# Sheet1.net
KiCad netlist of a schematic drawn in Altium Designer
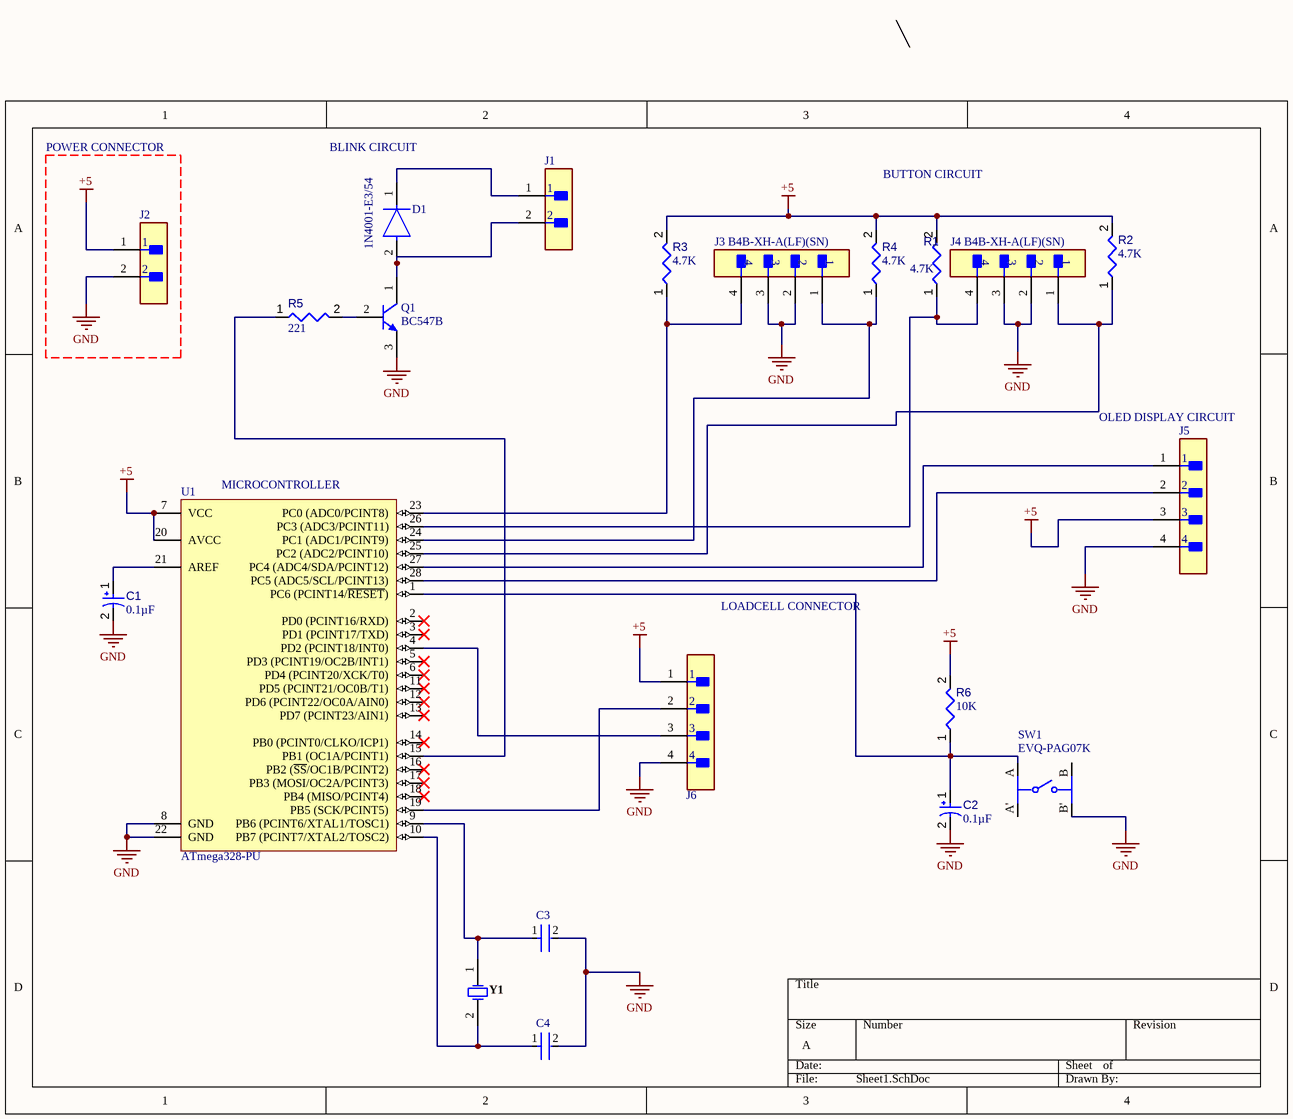
[diagram p0: Sheet1.SchDoc]

(export (version "E")
  (design (tool "Eeschema 10.0.6"))
  (components
    (comp (ref "C1")
      (value "0.1µF")
      (footprint "CAPPR55-200-1100X500X1200")
      (description "Aluminum Electrolytic Capacitor, 1 uF, +/- 20%, 50 V, -55 to 105 degC, 2-Pin THD, RoHS, Bulk")
      (fields (field (name "TOLERANCE") "20%") (field (name "MANUFACTURER") "Panasonic"))
      (libsource (lib "University of Moratuwa") (part "CAP-P-2"))
    )
    (comp (ref "C2")
      (value "0.1µF")
      (footprint "CAPPR55-200-1100X500X1200")
      (description "Aluminum Electrolytic Capacitor, 1 uF, +/- 20%, 50 V, -55 to 105 degC, 2-Pin THD, RoHS, Bulk")
      (fields (field (name "TOLERANCE") "20%") (field (name "MANUFACTURER") "Panasonic"))
      (libsource (lib "University of Moratuwa") (part "CAP-P-2"))
    )
    (comp (ref "C3")
      (value "RCE5C1H220J0M1H03A")
      (footprint "FP-RCE0K1-MFG")
      (description "Cap Ceramic 22pF 50V C0G ±5% Radial 5mm +125°C Automotive Bulk")
      (fields (field (name "TOLERANCE") "5%"))
      (libsource (lib "Altium Content Vault") (part "b4654b650e69147ec39a6b967a45e02"))
    )
    (comp (ref "C4")
      (value "RCE5C1H220J0M1H03A")
      (footprint "FP-RCE0K1-MFG")
      (description "Cap Ceramic 22pF 50V C0G ±5% Radial 5mm +125°C Automotive Bulk")
      (fields (field (name "TOLERANCE") "5%"))
      (libsource (lib "Altium Content Vault") (part "b4654b650e69147ec39a6b967a45e02"))
    )
    (comp (ref "D1")
      (value "1N4001-E3/54")
      (footprint "FP-1N4001-E3-54-MFG")
      (description "DIODE GEN PURP 50V 1A DO204AL")
      (fields (field (name "VOLTAGE") "50V"))
      (libsource (lib "Altium Content Vault") (part "d7152d700b627762746794eb795d46e"))
    )
    (comp (ref "J1")
      (value "~")
      (footprint "FP-B2B-XH-A_LF_SN-MFG")
      (description "CONN HEADER VERT 2POS 2.5MM")
      (libsource (lib "Altium Content Vault") (part "3bc925449376181038e59eaffc5286c"))
    )
    (comp (ref "J2")
      (value "~")
      (footprint "FP-B2B-XH-A_LF_SN-MFG")
      (description "CONN HEADER VERT 2POS 2.5MM")
      (libsource (lib "Altium Content Vault") (part "3bc925449376181038e59eaffc5286c"))
    )
    (comp (ref "J3")
      (value "B4B-XH-A(LF)(SN)")
      (footprint "FP-B4B-XH-A_LF_SN-MFG")
      (description "CONN HEADER VERT 4POS 2.5MM")
      (libsource (lib "Altium Content Vault") (part "299a8cea1bdcbc3624fe62c390fa72c"))
    )
    (comp (ref "J4")
      (value "B4B-XH-A(LF)(SN)")
      (footprint "FP-B4B-XH-A_LF_SN-MFG")
      (description "CONN HEADER VERT 4POS 2.5MM")
      (libsource (lib "Altium Content Vault") (part "299a8cea1bdcbc3624fe62c390fa72c"))
    )
    (comp (ref "J5")
      (value "B4B-XH-A(LF)(SN)")
      (footprint "FP-B4B-XH-A_LF_SN-MFG")
      (description "CONN HEADER VERT 4POS 2.5MM")
      (libsource (lib "Altium Content Vault") (part "299a8cea1bdcbc3624fe62c390fa72c"))
    )
    (comp (ref "J6")
      (value "B4B-XH-A(LF)(SN)")
      (footprint "FP-B4B-XH-A_LF_SN-MFG")
      (description "CONN HEADER VERT 4POS 2.5MM")
      (libsource (lib "Altium Content Vault") (part "299a8cea1bdcbc3624fe62c390fa72c"))
    )
    (comp (ref "Q1")
      (value "BC547B")
      (footprint "ONSC-TO-92-3-29-11")
      (description "Amplifier Transistor, NPN Silicon, 3-Pin TO-92, Bulk Box")
      (fields (field (name "MANUFACTURER") "On Semiconductor"))
      (libsource (lib "Altium Content Vault") (part "ONSC-NPN-C1B2E3-3"))
    )
    (comp (ref "R1")
      (value "4.7K")
      (footprint "RESA60-630X240")
      (description "Axial Resistor, 22.1 Ohm, +/- 1%, 250 mW, -55 to 155 degC, 2-Pin THD, RoHS, Bulk")
      (fields (field (name "POWER") "250mW") (field (name "MANUFACTURER") "Yageo"))
      (libsource (lib "University of Moratuwa") (part "RES-2"))
    )
    (comp (ref "R2")
      (value "4.7K")
      (footprint "RESA60-630X240")
      (description "Axial Resistor, 22.1 Ohm, +/- 1%, 250 mW, -55 to 155 degC, 2-Pin THD, RoHS, Bulk")
      (fields (field (name "POWER") "250mW") (field (name "MANUFACTURER") "Yageo"))
      (libsource (lib "University of Moratuwa") (part "RES-2"))
    )
    (comp (ref "R3")
      (value "4.7K")
      (footprint "RESA60-630X240")
      (description "Axial Resistor, 22.1 Ohm, +/- 1%, 250 mW, -55 to 155 degC, 2-Pin THD, RoHS, Bulk")
      (fields (field (name "POWER") "250mW") (field (name "MANUFACTURER") "Yageo"))
      (libsource (lib "University of Moratuwa") (part "RES-2"))
    )
    (comp (ref "R4")
      (value "4.7K")
      (footprint "RESA60-630X240")
      (description "Axial Resistor, 22.1 Ohm, +/- 1%, 250 mW, -55 to 155 degC, 2-Pin THD, RoHS, Bulk")
      (fields (field (name "POWER") "250mW") (field (name "MANUFACTURER") "Yageo"))
      (libsource (lib "University of Moratuwa") (part "RES-2"))
    )
    (comp (ref "R5")
      (value "221")
      (footprint "RESA60-630X240")
      (description "Axial Resistor, 221 Ohm, +/- 1%, 250 mW, -55 to 155 degC, 2-Pin THD, RoHS, Bulk")
      (fields (field (name "POWER") "250mW") (field (name "TOLERANCE") "1%"))
      (libsource (lib "University of Moratuwa") (part "RES-2"))
    )
    (comp (ref "R6")
      (value "10K")
      (footprint "RESA60-630X240")
      (description "Axial Resistor, 22.1 Ohm, +/- 1%, 250 mW, -55 to 155 degC, 2-Pin THD, RoHS, Bulk")
      (fields (field (name "POWER") "250mW") (field (name "MANUFACTURER") "Yageo"))
      (libsource (lib "University of Moratuwa") (part "RES-2"))
    )
    (comp (ref "SW1")
      (value "EVQ-PAG07K")
      (footprint "FP-EVQ-PAG07K-MFG")
      (description "SWITCH TACTILE SPST-NO 0.02A 15V")
      (libsource (lib "Altium Content Vault") (part "75038bc65b1af1a6bd057da08483287"))
    )
    (comp (ref "U1")
      (value "ATmega328-PU")
      (footprint "28P3")
      (libsource (lib "Altium Content Vault") (part "MC-8B-ATM48-IL28"))
    )
    (comp (ref "Y1")
      (value "HC-49US 16.000MHZ")
      (footprint "JPY-HC-49US")
      (description "Crystal, 16 MHz, +/- 30 ppm, 18 pF, -20 to 70 degC, 2-Pin THD")
      (fields (field (name "MANUFACTURER") "Jing peng yuan"))
      (libsource (lib "University of Moratuwa") (part "XTAL-1-2-2"))
    )
  )
  (nets
    (net (code "1") (name "+5") (class "Default")
      (node (ref "J2") (pin "1") (pinfunction "1_1") (pintype "passive"))
      (node (ref "J5") (pin "3") (pinfunction "3_3") (pintype "passive"))
      (node (ref "J6") (pin "1") (pinfunction "1_1") (pintype "passive"))
      (node (ref "R1") (pin "2") (pinfunction "2_2") (pintype "passive"))
      (node (ref "R2") (pin "2") (pinfunction "2_2") (pintype "passive"))
      (node (ref "R3") (pin "2") (pinfunction "2_2") (pintype "passive"))
      (node (ref "R4") (pin "2") (pinfunction "2_2") (pintype "passive"))
      (node (ref "R6") (pin "2") (pinfunction "2_2") (pintype "passive"))
      (node (ref "U1") (pin "20") (pinfunction "AVCC_20") (pintype "power_in"))
      (node (ref "U1") (pin "7") (pinfunction "VCC_7") (pintype "power_in"))
    )
    (net (code "2") (name "GND") (class "Default")
      (node (ref "C1") (pin "2") (pinfunction "2_2") (pintype "passive"))
      (node (ref "C2") (pin "2") (pinfunction "2_2") (pintype "passive"))
      (node (ref "C3") (pin "2") (pinfunction "2_2") (pintype "passive"))
      (node (ref "C4") (pin "2") (pinfunction "2_2") (pintype "passive"))
      (node (ref "J2") (pin "2") (pinfunction "2_2") (pintype "passive"))
      (node (ref "J3") (pin "2") (pinfunction "2_2") (pintype "passive"))
      (node (ref "J3") (pin "3") (pinfunction "3_3") (pintype "passive"))
      (node (ref "J4") (pin "2") (pinfunction "2_2") (pintype "passive"))
      (node (ref "J4") (pin "3") (pinfunction "3_3") (pintype "passive"))
      (node (ref "J5") (pin "4") (pinfunction "4_4") (pintype "passive"))
      (node (ref "J6") (pin "4") (pinfunction "4_4") (pintype "passive"))
      (node (ref "Q1") (pin "3") (pinfunction "E_3") (pintype "passive"))
      (node (ref "SW1") (pin "B'") (pinfunction "B'_B'") (pintype "passive"))
      (node (ref "U1") (pin "22") (pinfunction "GND_22") (pintype "power_in"))
      (node (ref "U1") (pin "8") (pinfunction "GND_8") (pintype "power_in"))
    )
    (net (code "3") (name "Net-(D1-A)") (class "Default")
      (node (ref "D1") (pin "2") (pinfunction "A_2") (pintype "passive"))
      (node (ref "J1") (pin "2") (pinfunction "2_2") (pintype "passive"))
      (node (ref "Q1") (pin "1") (pinfunction "C_1") (pintype "passive"))
    )
    (net (code "4") (name "Net-(D1-C)") (class "Default")
      (node (ref "D1") (pin "1") (pinfunction "C_1") (pintype "passive"))
      (node (ref "J1") (pin "1") (pinfunction "1_1") (pintype "passive"))
    )
    (net (code "5") (name "Net-(Q1-B)") (class "Default")
      (node (ref "Q1") (pin "2") (pinfunction "B_2") (pintype "passive"))
      (node (ref "R5") (pin "2") (pinfunction "2_2") (pintype "passive"))
    )
    (net (code "6") (name "Net-(U1-AREF)") (class "Default")
      (node (ref "C1") (pin "1") (pinfunction "1_1") (pintype "passive"))
      (node (ref "U1") (pin "21") (pinfunction "AREF_21") (pintype "power_in"))
    )
    (net (code "7") (name "Net-(U1-PB1_(OC1A{slash}PCINT1))") (class "Default")
      (node (ref "R5") (pin "1") (pinfunction "1_1") (pintype "passive"))
      (node (ref "U1") (pin "15") (pinfunction "PB1_(OC1A/PCINT1)_15") (pintype "bidirectional"))
    )
    (net (code "8") (name "Net-(U1-PB5_(SCK{slash}PCINT5))") (class "Default")
      (node (ref "J6") (pin "2") (pinfunction "2_2") (pintype "passive"))
      (node (ref "U1") (pin "19") (pinfunction "PB5_(SCK/PCINT5)_19") (pintype "bidirectional"))
    )
    (net (code "9") (name "Net-(U1-PB6_(PCINT6{slash}XTAL1{slash}TOSC1))") (class "Default")
      (node (ref "C3") (pin "1") (pinfunction "1_1") (pintype "passive"))
      (node (ref "U1") (pin "9") (pinfunction "PB6_(PCINT6/XTAL1/TOSC1)_9") (pintype "bidirectional"))
      (node (ref "Y1") (pin "1") (pinfunction "1_1") (pintype "passive"))
    )
    (net (code "10") (name "Net-(U1-PB7_(PCINT7{slash}XTAL2{slash}TOSC2))") (class "Default")
      (node (ref "C4") (pin "1") (pinfunction "1_1") (pintype "passive"))
      (node (ref "U1") (pin "10") (pinfunction "PB7_(PCINT7/XTAL2/TOSC2)_10") (pintype "bidirectional"))
      (node (ref "Y1") (pin "2") (pinfunction "2_2") (pintype "passive"))
    )
    (net (code "11") (name "Net-(U1-PC0_(ADC0{slash}PCINT8))") (class "Default")
      (node (ref "J3") (pin "4") (pinfunction "4_4") (pintype "passive"))
      (node (ref "R3") (pin "1") (pinfunction "1_1") (pintype "passive"))
      (node (ref "U1") (pin "23") (pinfunction "PC0_(ADC0/PCINT8)_23") (pintype "bidirectional"))
    )
    (net (code "12") (name "Net-(U1-PC1_(ADC1{slash}PCINT9))") (class "Default")
      (node (ref "J3") (pin "1") (pinfunction "1_1") (pintype "passive"))
      (node (ref "R4") (pin "1") (pinfunction "1_1") (pintype "passive"))
      (node (ref "U1") (pin "24") (pinfunction "PC1_(ADC1/PCINT9)_24") (pintype "bidirectional"))
    )
    (net (code "13") (name "Net-(U1-PC2_(ADC2{slash}PCINT10))") (class "Default")
      (node (ref "J4") (pin "1") (pinfunction "1_1") (pintype "passive"))
      (node (ref "R2") (pin "1") (pinfunction "1_1") (pintype "passive"))
      (node (ref "U1") (pin "25") (pinfunction "PC2_(ADC2/PCINT10)_25") (pintype "bidirectional"))
    )
    (net (code "14") (name "Net-(U1-PC3_(ADC3{slash}PCINT11))") (class "Default")
      (node (ref "J4") (pin "4") (pinfunction "4_4") (pintype "passive"))
      (node (ref "R1") (pin "1") (pinfunction "1_1") (pintype "passive"))
      (node (ref "U1") (pin "26") (pinfunction "PC3_(ADC3/PCINT11)_26") (pintype "bidirectional"))
    )
    (net (code "15") (name "Net-(U1-PC4_(ADC4{slash}SDA{slash}PCINT12))") (class "Default")
      (node (ref "J5") (pin "1") (pinfunction "1_1") (pintype "passive"))
      (node (ref "U1") (pin "27") (pinfunction "PC4_(ADC4/SDA/PCINT12)_27") (pintype "bidirectional"))
    )
    (net (code "16") (name "Net-(U1-PC5_(ADC5{slash}SCL{slash}PCINT13))") (class "Default")
      (node (ref "J5") (pin "2") (pinfunction "2_2") (pintype "passive"))
      (node (ref "U1") (pin "28") (pinfunction "PC5_(ADC5/SCL/PCINT13)_28") (pintype "bidirectional"))
    )
    (net (code "17") (name "Net-(U1-PC6_(PCINT14{slash}~{RESET}))") (class "Default")
      (node (ref "C2") (pin "1") (pinfunction "1_1") (pintype "passive"))
      (node (ref "R6") (pin "1") (pinfunction "1_1") (pintype "passive"))
      (node (ref "SW1") (pin "A") (pinfunction "A_A") (pintype "passive"))
      (node (ref "U1") (pin "1") (pinfunction "PC6_(PCINT14/~{RESET})_1") (pintype "bidirectional"))
    )
    (net (code "18") (name "Net-(U1-PD2_(PCINT18{slash}INT0))") (class "Default")
      (node (ref "J6") (pin "3") (pinfunction "3_3") (pintype "passive"))
      (node (ref "U1") (pin "4") (pinfunction "PD2_(PCINT18/INT0)_4") (pintype "bidirectional"))
    )
    (net (code "19") (name "unconnected-(SW1-PadA')") (class "Default")
      (node (ref "SW1") (pin "A'") (pinfunction "A'_A'") (pintype "passive"))
    )
    (net (code "20") (name "unconnected-(SW1-PadB)") (class "Default")
      (node (ref "SW1") (pin "B") (pinfunction "B_B") (pintype "passive"))
    )
    (net (code "21") (name "unconnected-(U1-PB0_(PCINT0{slash}CLKO{slash}ICP1)-Pad14)") (class "Default")
      (node (ref "U1") (pin "14") (pinfunction "PB0_(PCINT0/CLKO/ICP1)_14") (pintype "bidirectional+no_connect"))
    )
    (net (code "22") (name "unconnected-(U1-PB2_(~{SS}{slash}OC1B{slash}PCINT2)-Pad16)") (class "Default")
      (node (ref "U1") (pin "16") (pinfunction "PB2_(~{SS}/OC1B/PCINT2)_16") (pintype "bidirectional+no_connect"))
    )
    (net (code "23") (name "unconnected-(U1-PB3_(MOSI{slash}OC2A{slash}PCINT3)-Pad17)") (class "Default")
      (node (ref "U1") (pin "17") (pinfunction "PB3_(MOSI/OC2A/PCINT3)_17") (pintype "bidirectional+no_connect"))
    )
    (net (code "24") (name "unconnected-(U1-PB4_(MISO{slash}PCINT4)-Pad18)") (class "Default")
      (node (ref "U1") (pin "18") (pinfunction "PB4_(MISO/PCINT4)_18") (pintype "bidirectional+no_connect"))
    )
    (net (code "25") (name "unconnected-(U1-PD0_(PCINT16{slash}RXD)-Pad2)") (class "Default")
      (node (ref "U1") (pin "2") (pinfunction "PD0_(PCINT16/RXD)_2") (pintype "bidirectional+no_connect"))
    )
    (net (code "26") (name "unconnected-(U1-PD1_(PCINT17{slash}TXD)-Pad3)") (class "Default")
      (node (ref "U1") (pin "3") (pinfunction "PD1_(PCINT17/TXD)_3") (pintype "bidirectional+no_connect"))
    )
    (net (code "27") (name "unconnected-(U1-PD3_(PCINT19{slash}OC2B{slash}INT1)-Pad5)") (class "Default")
      (node (ref "U1") (pin "5") (pinfunction "PD3_(PCINT19/OC2B/INT1)_5") (pintype "bidirectional+no_connect"))
    )
    (net (code "28") (name "unconnected-(U1-PD4_(PCINT20{slash}XCK{slash}T0)-Pad6)") (class "Default")
      (node (ref "U1") (pin "6") (pinfunction "PD4_(PCINT20/XCK/T0)_6") (pintype "bidirectional+no_connect"))
    )
    (net (code "29") (name "unconnected-(U1-PD5_(PCINT21{slash}OC0B{slash}T1)-Pad11)") (class "Default")
      (node (ref "U1") (pin "11") (pinfunction "PD5_(PCINT21/OC0B/T1)_11") (pintype "bidirectional+no_connect"))
    )
    (net (code "30") (name "unconnected-(U1-PD6_(PCINT22{slash}OC0A{slash}AIN0)-Pad12)") (class "Default")
      (node (ref "U1") (pin "12") (pinfunction "PD6_(PCINT22/OC0A/AIN0)_12") (pintype "bidirectional+no_connect"))
    )
    (net (code "31") (name "unconnected-(U1-PD7_(PCINT23{slash}AIN1)-Pad13)") (class "Default")
      (node (ref "U1") (pin "13") (pinfunction "PD7_(PCINT23/AIN1)_13") (pintype "bidirectional+no_connect"))
    )
  )
)
